# AS5048B_Encoder_board.net
KiCad netlist of a schematic drawn in EAGLE
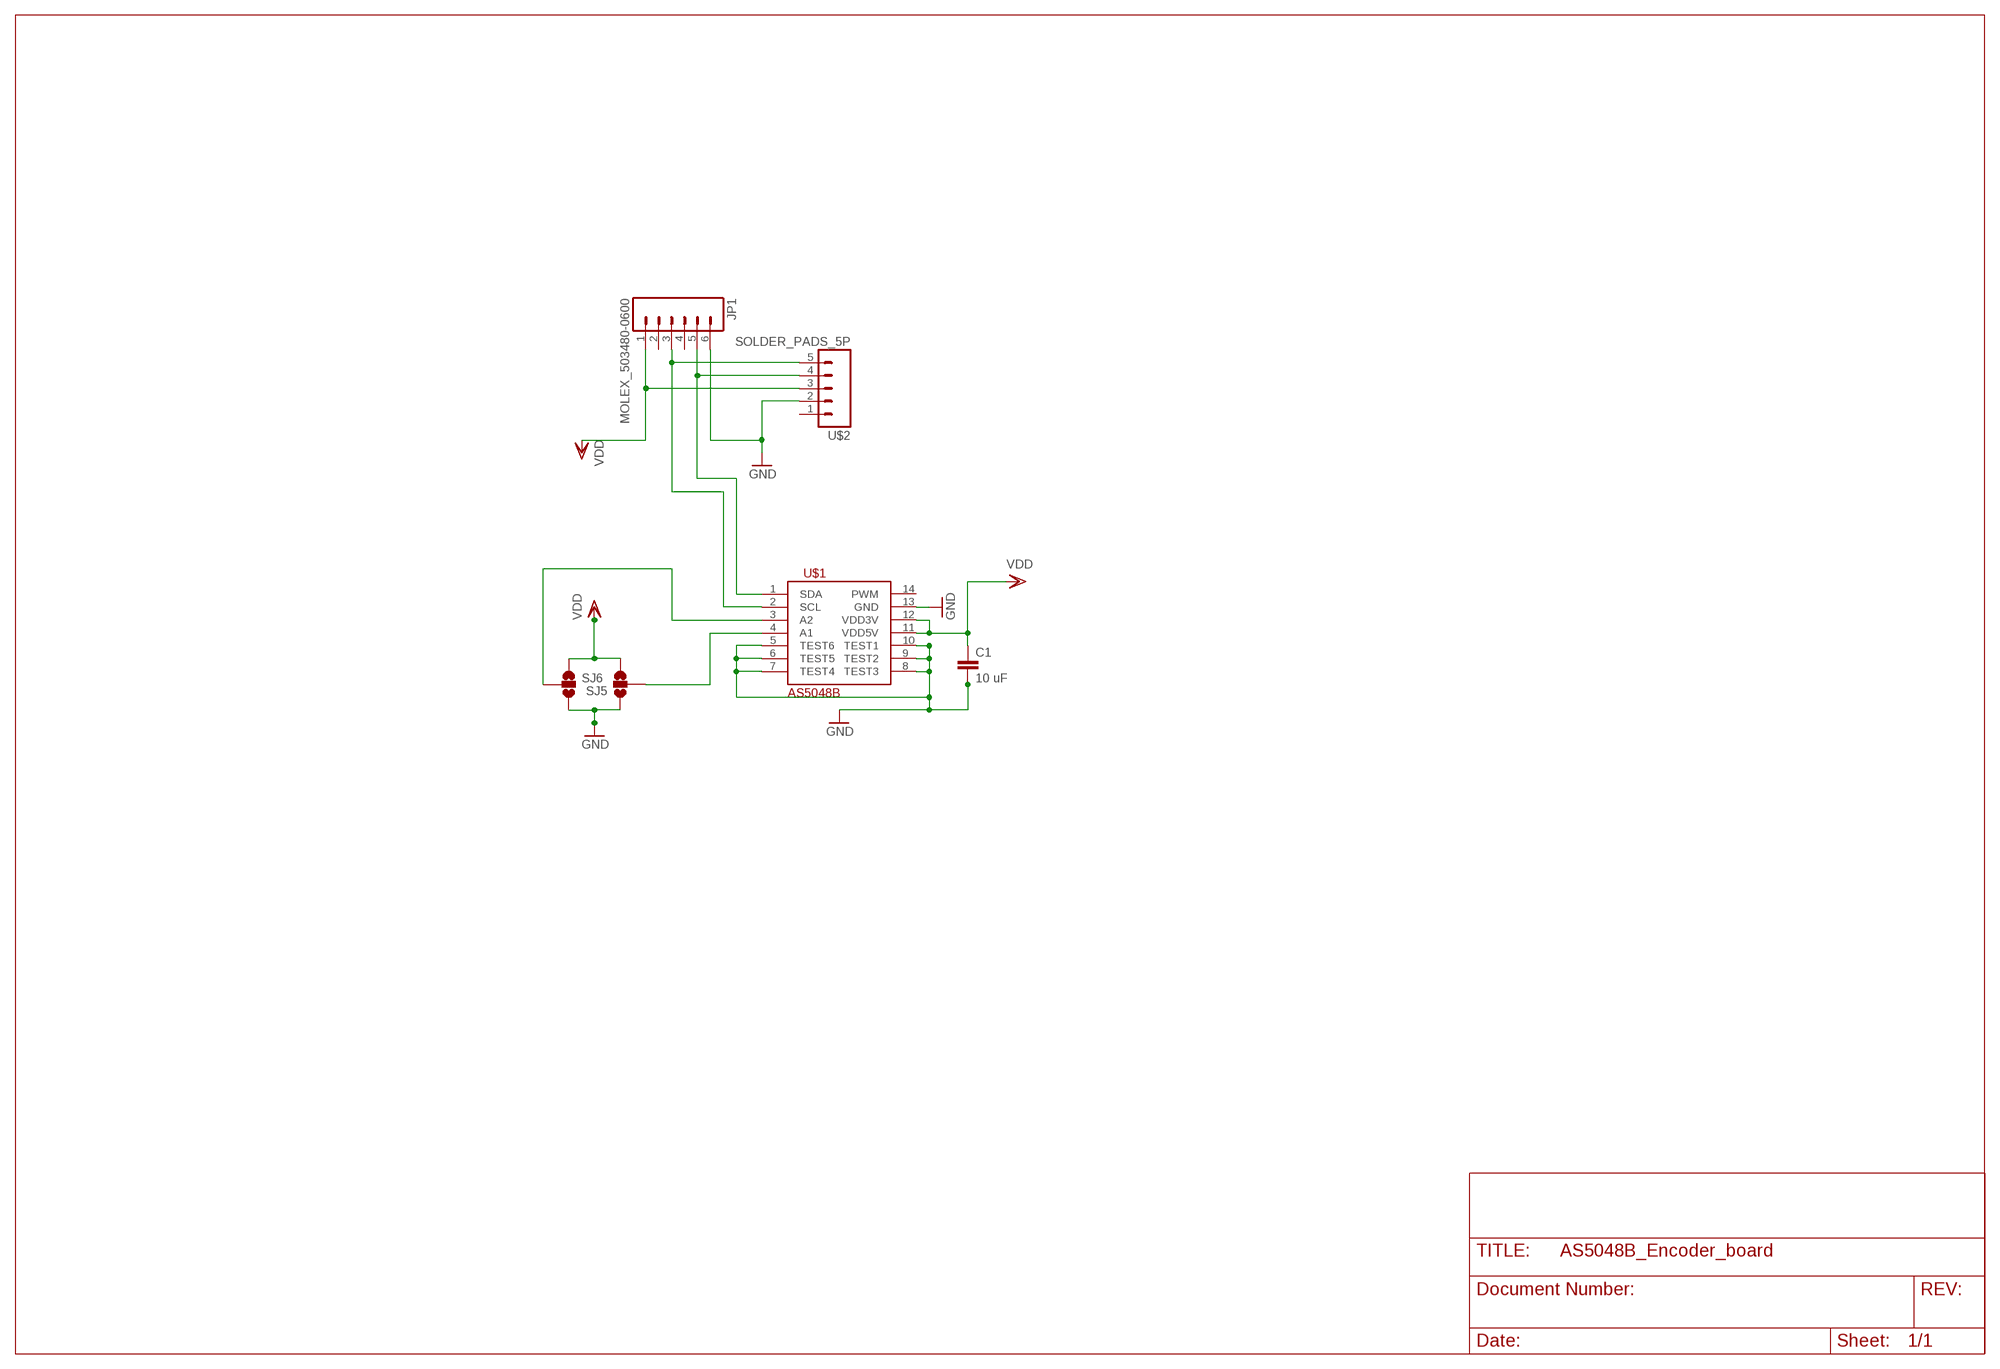
[diagram p0: schematic, sheet 1]

(export (version "E")
  (design (tool "Eeschema 10.0.6"))
  (components
    (comp (ref "C1")
      (value "10 uF")
      (footprint "eagle-import:0603-CAP")
      (libsource (lib "eagle-import") (part "CAP0603-CAP"))
    )
    (comp (ref "JP1")
      (value "MOLEX_503480-0600")
      (footprint "eagle-import:MOLEX_503480-0600")
      (libsource (lib "eagle-import") (part "MOLEX_503480-0600"))
    )
    (comp (ref "SJ5")
      (value "SOLDERJUMPER_2WAYS")
      (footprint "eagle-import:SJ_3")
      (libsource (lib "eagle-import") (part "SOLDERJUMPER_2WAYS"))
    )
    (comp (ref "SJ6")
      (value "SOLDERJUMPER_2WAYS")
      (footprint "eagle-import:SJ_3")
      (libsource (lib "eagle-import") (part "SOLDERJUMPER_2WAYS"))
    )
    (comp (ref "U$1")
      (value "AS5048B")
      (footprint "eagle-import:TSSOP14")
      (libsource (lib "eagle-import") (part "AS5048B"))
    )
    (comp (ref "U$2")
      (value "SOLDER_PADS_5P")
      (footprint "eagle-import:SOLDER_PADS_5P")
      (libsource (lib "eagle-import") (part "SOLDER_PADS_5P"))
    )
  )
  (nets
    (net (code "1") (name "GND") (class "Default")
      (node (ref "C1") (pin "2") (pinfunction "2_2") (pintype "passive"))
      (node (ref "JP1") (pin "6") (pinfunction "6_6") (pintype "passive"))
      (node (ref "SJ5") (pin "1") (pinfunction "1_1") (pintype "passive"))
      (node (ref "SJ6") (pin "3") (pinfunction "3_3") (pintype "passive"))
      (node (ref "U$1") (pin "10") (pinfunction "TEST1_10") (pintype "bidirectional"))
      (node (ref "U$1") (pin "13") (pinfunction "GND_13") (pintype "bidirectional"))
      (node (ref "U$1") (pin "5") (pinfunction "TEST6_5") (pintype "bidirectional"))
      (node (ref "U$1") (pin "6") (pinfunction "TEST5_6") (pintype "bidirectional"))
      (node (ref "U$1") (pin "7") (pinfunction "TEST4_7") (pintype "bidirectional"))
      (node (ref "U$1") (pin "8") (pinfunction "TEST3_8") (pintype "bidirectional"))
      (node (ref "U$1") (pin "9") (pinfunction "TEST2_9") (pintype "bidirectional"))
      (node (ref "U$2") (pin "2") (pinfunction "2_2") (pintype "passive"))
    )
    (net (code "2") (name "Net-(U$1-A1)") (class "Default")
      (node (ref "SJ5") (pin "2") (pinfunction "2_2") (pintype "passive"))
      (node (ref "U$1") (pin "4") (pinfunction "A1_4") (pintype "bidirectional"))
    )
    (net (code "3") (name "Net-(U$1-A2)") (class "Default")
      (node (ref "SJ6") (pin "2") (pinfunction "2_2") (pintype "passive"))
      (node (ref "U$1") (pin "3") (pinfunction "A2_3") (pintype "bidirectional"))
    )
    (net (code "4") (name "Net-(U$1-SCL)") (class "Default")
      (node (ref "JP1") (pin "3") (pinfunction "3_3") (pintype "passive"))
      (node (ref "U$1") (pin "2") (pinfunction "SCL_2") (pintype "bidirectional"))
      (node (ref "U$2") (pin "5") (pinfunction "5_5") (pintype "passive"))
    )
    (net (code "5") (name "Net-(U$1-SDA)") (class "Default")
      (node (ref "JP1") (pin "5") (pinfunction "5_5") (pintype "passive"))
      (node (ref "U$1") (pin "1") (pinfunction "SDA_1") (pintype "bidirectional"))
      (node (ref "U$2") (pin "4") (pinfunction "4_4") (pintype "passive"))
    )
    (net (code "6") (name "VDD") (class "Default")
      (node (ref "C1") (pin "1") (pinfunction "1_1") (pintype "passive"))
      (node (ref "JP1") (pin "1") (pinfunction "1_1") (pintype "passive"))
      (node (ref "SJ5") (pin "3") (pinfunction "3_3") (pintype "passive"))
      (node (ref "SJ6") (pin "1") (pinfunction "1_1") (pintype "passive"))
      (node (ref "U$1") (pin "11") (pinfunction "VDD5V_11") (pintype "bidirectional"))
      (node (ref "U$1") (pin "12") (pinfunction "VDD3V_12") (pintype "bidirectional"))
      (node (ref "U$2") (pin "3") (pinfunction "3_3") (pintype "passive"))
    )
    (net (code "7") (name "unconnected-(JP1-Pad2)") (class "Default")
      (node (ref "JP1") (pin "2") (pinfunction "2_2") (pintype "passive"))
    )
    (net (code "8") (name "unconnected-(JP1-Pad4)") (class "Default")
      (node (ref "JP1") (pin "4") (pinfunction "4_4") (pintype "passive"))
    )
    (net (code "9") (name "unconnected-(U$1-PWM-Pad14)") (class "Default")
      (node (ref "U$1") (pin "14") (pinfunction "PWM_14") (pintype "bidirectional"))
    )
    (net (code "10") (name "unconnected-(U$2-Pad1)") (class "Default")
      (node (ref "U$2") (pin "1") (pinfunction "1_1") (pintype "passive"))
    )
  )
)
